# design.net
KiCad netlist of a schematic drawn in EasyEDA
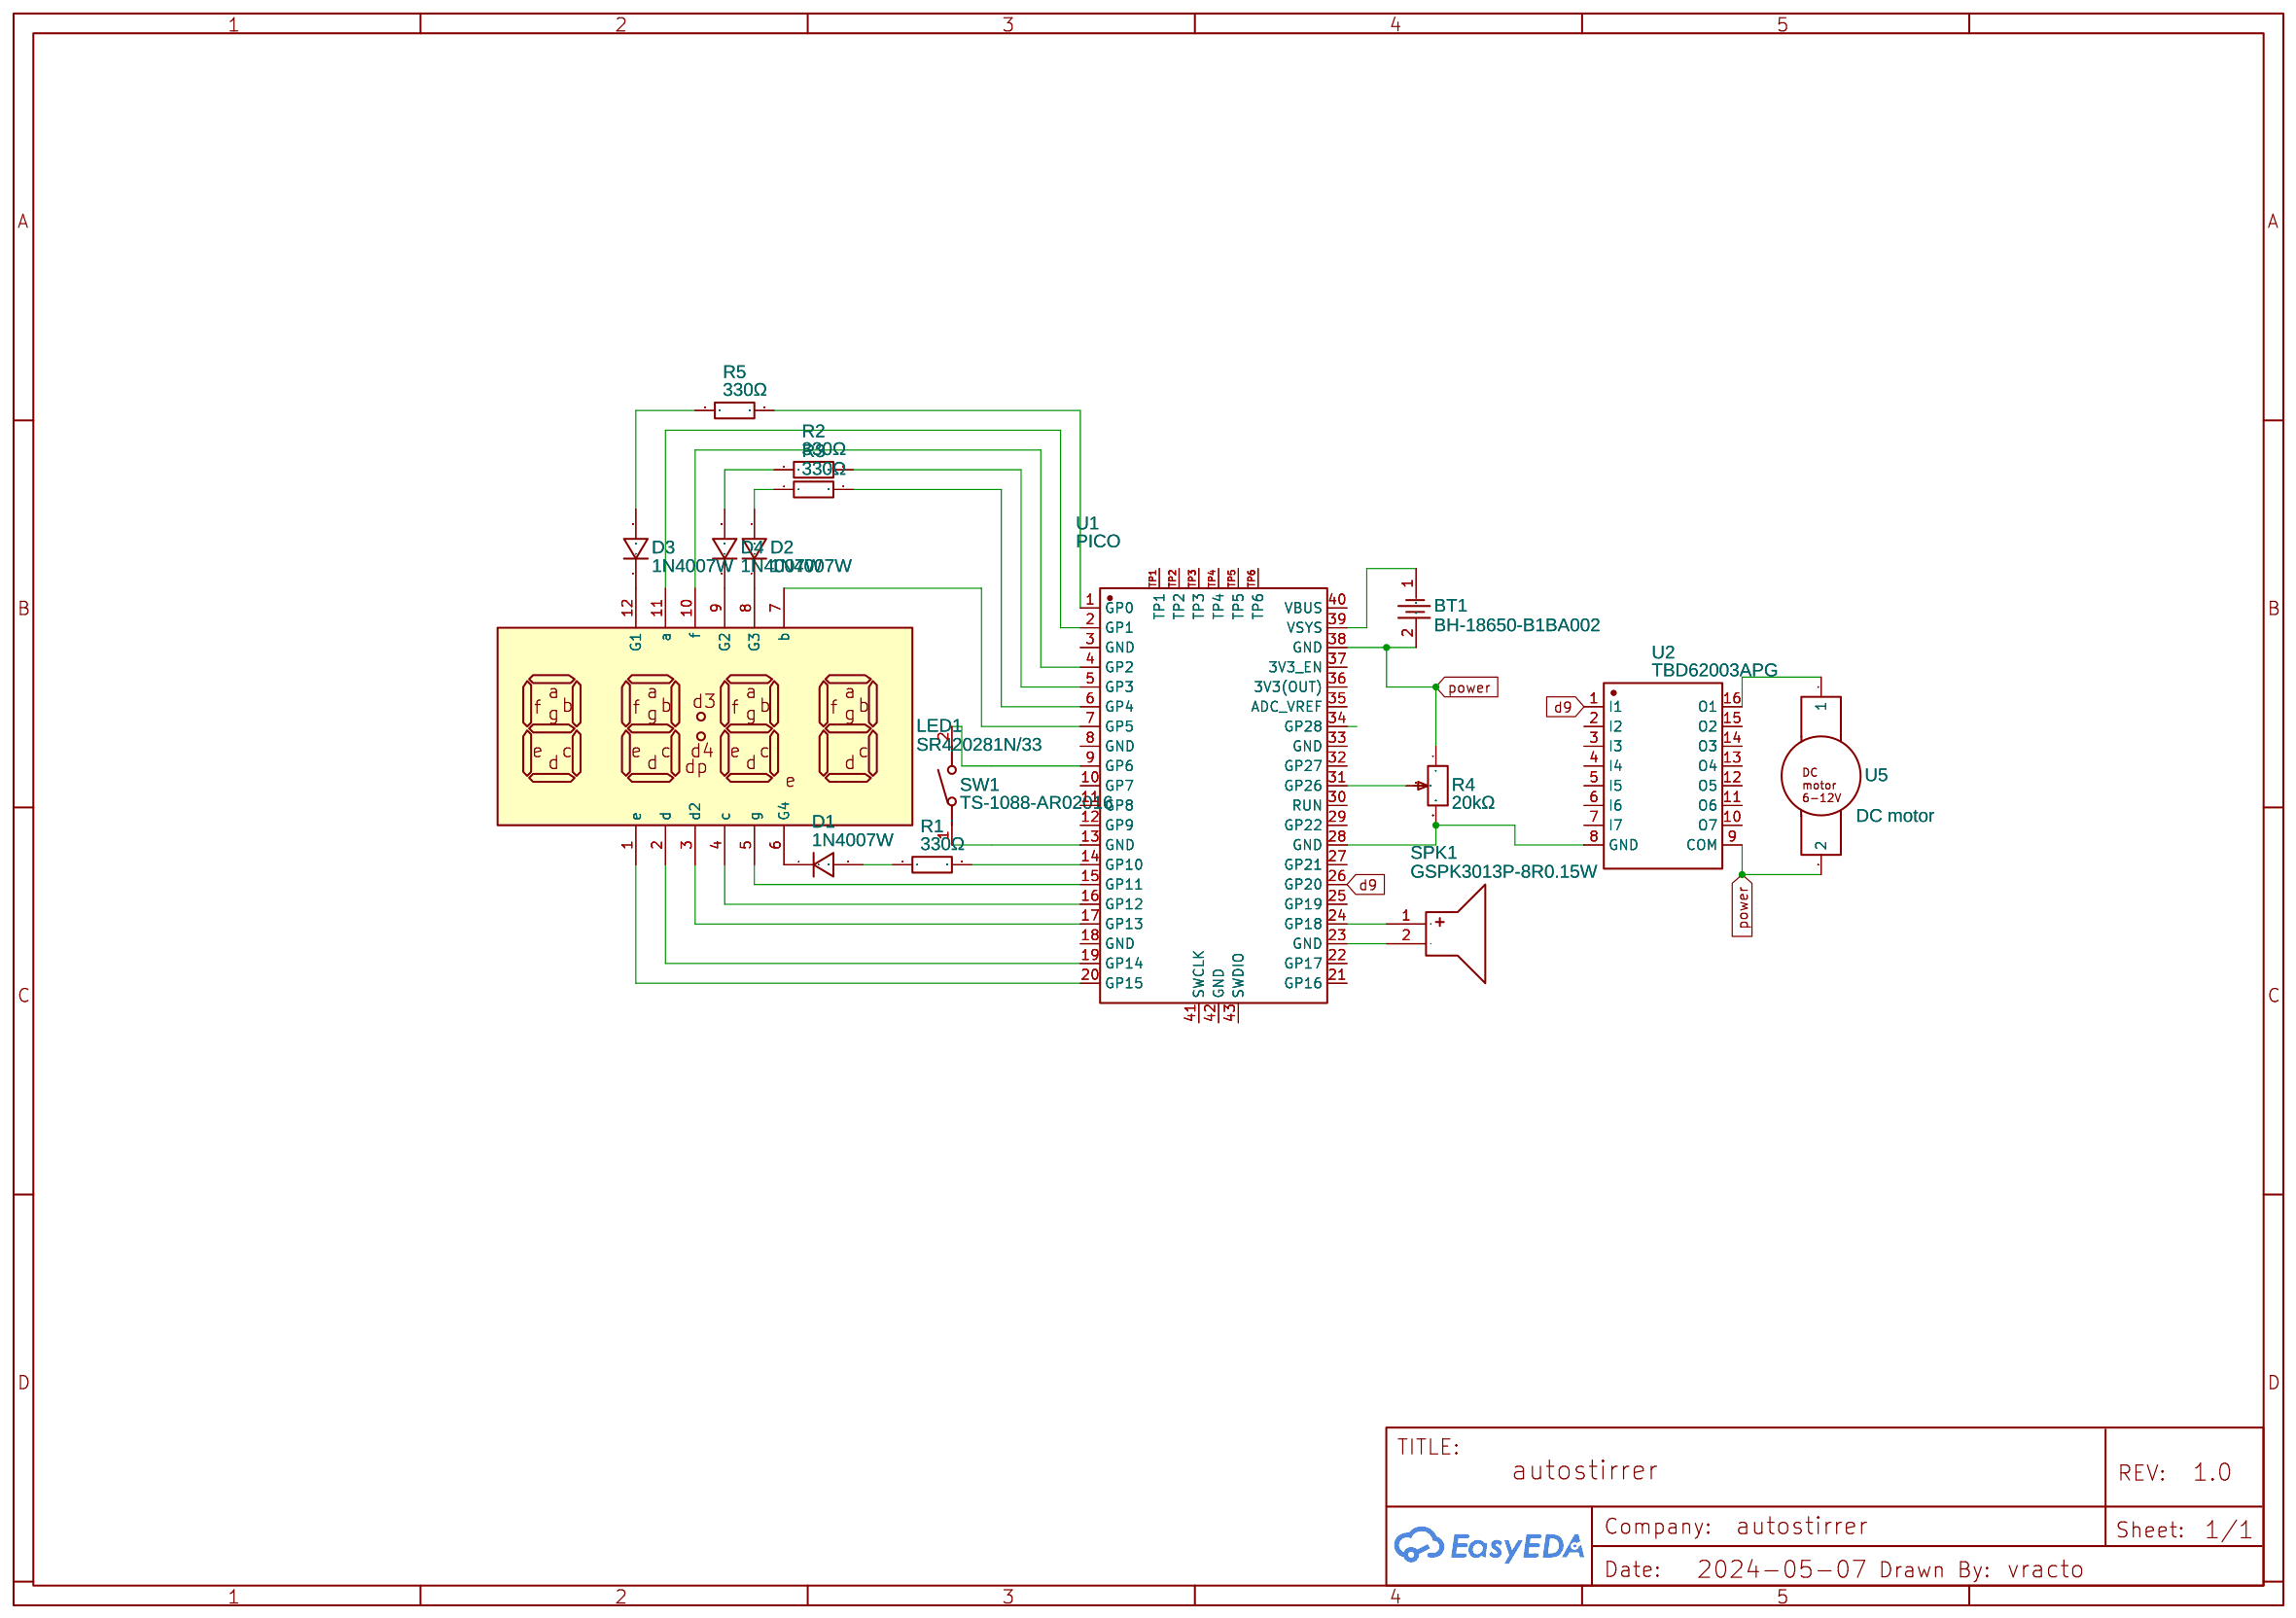
[diagram p0: schematic sheet]

(export (version "E")
  (design (tool "Eeschema 10.0.6"))
  (components
    (comp (ref "BT1")
      (value "BH-18650-B1BA002")
      (fields (field (name "Manufacturer") "MYOUNG(美阳)"))
      (libsource (lib "") (part "BH-18650-B1BA002"))
    )
    (comp (ref "D1")
      (value "1N4007W")
      (fields (field (name "Manufacturer") "BLUE ROCKET"))
      (libsource (lib "") (part "1N4007W_1"))
    )
    (comp (ref "D2")
      (value "1N4007W")
      (fields (field (name "Manufacturer") "BLUE ROCKET"))
      (libsource (lib "") (part "1N4007W"))
    )
    (comp (ref "D3")
      (value "1N4007W")
      (fields (field (name "Manufacturer") "BLUE ROCKET"))
      (libsource (lib "") (part "1N4007W"))
    )
    (comp (ref "D4")
      (value "1N4007W")
      (fields (field (name "Manufacturer") "BLUE ROCKET"))
      (libsource (lib "") (part "1N4007W"))
    )
    (comp (ref "LED1")
      (value "SR420281N/33")
      (fields (field (name "Manufacturer Part") "SR420281N") (field (name "Manufacturer") "ARKLED(方舟)"))
      (libsource (lib "") (part "SR420281N/33"))
    )
    (comp (ref "R1")
      (value "330Ω")
      (fields (field (name "Manufacturer Part") "MFR-25FTE52-330R") (field (name "Manufacturer") "YAGEO(国巨)"))
      (libsource (lib "") (part "MFR-25FTE52-330R"))
    )
    (comp (ref "R2")
      (value "330Ω")
      (fields (field (name "Manufacturer Part") "MFR-25FTE52-330R") (field (name "Manufacturer") "YAGEO(国巨)"))
      (libsource (lib "") (part "MFR-25FTE52-330R"))
    )
    (comp (ref "R3")
      (value "330Ω")
      (fields (field (name "Manufacturer Part") "MFR-25FTE52-330R") (field (name "Manufacturer") "YAGEO(国巨)"))
      (libsource (lib "") (part "MFR-25FTE52-330R"))
    )
    (comp (ref "R4")
      (value "20kΩ")
      (fields (field (name "Manufacturer Part") "3296W-1-203LF") (field (name "Manufacturer") "BOURNS"))
      (libsource (lib "") (part "3296W-1-203LF"))
    )
    (comp (ref "R5")
      (value "330Ω")
      (fields (field (name "Manufacturer Part") "MFR-25FTE52-330R") (field (name "Manufacturer") "YAGEO(国巨)"))
      (libsource (lib "") (part "MFR-25FTE52-330R"))
    )
    (comp (ref "SPK1")
      (value "GSPK3013P-8R0.15W")
      (fields (field (name "Manufacturer") "INGHAi(赢海)"))
      (libsource (lib "") (part "GSPK3013P-8R0.15W"))
    )
    (comp (ref "SW1")
      (value "TS-1088-AR02016")
      (fields (field (name "Manufacturer") "XUNPU(讯普)"))
      (libsource (lib "") (part "TS-1088-AR02016"))
    )
    (comp (ref "U1")
      (value "PICO")
      (fields (field (name "Manufacturer") "Raspberry Pi(树莓派)"))
      (libsource (lib "") (part "PICO"))
    )
    (comp (ref "U2")
      (value "TBD62003APG")
      (fields
        (field (name "Manufacturer Part") "TBD62003APG(Z,HZ)")
        (field (name "Manufacturer") "TOSHIBA(东芝)")
      )
      (libsource (lib "") (part "TBD62003APG"))
    )
    (comp (ref "U5")
      (value "DC motor")
      (fields (field (name "Manufacturer Part") "?"))
      (libsource (lib "") (part "Unknown_915_-420"))
    )
  )
  (nets
    (net (code "1") (name "Net-(D1-Pad2)") (class "Default")
      (node (ref "D1") (pin "2") (pinfunction "2_2") (pintype "unspecified"))
      (node (ref "R1") (pin "1") (pinfunction "1_1") (pintype "input"))
    )
    (net (code "2") (name "Net-(D2-Pad2)") (class "Default")
      (node (ref "D2") (pin "2") (pinfunction "2_2") (pintype "unspecified"))
      (node (ref "R3") (pin "1") (pinfunction "1_1") (pintype "input"))
    )
    (net (code "3") (name "Net-(D3-Pad2)") (class "Default")
      (node (ref "D3") (pin "2") (pinfunction "2_2") (pintype "unspecified"))
      (node (ref "R5") (pin "1") (pinfunction "1_1") (pintype "input"))
    )
    (net (code "4") (name "Net-(D4-Pad2)") (class "Default")
      (node (ref "D4") (pin "2") (pinfunction "2_2") (pintype "unspecified"))
      (node (ref "R2") (pin "1") (pinfunction "1_1") (pintype "input"))
    )
    (net (code "5") (name "Net-(LED1-G1)") (class "Default")
      (node (ref "D3") (pin "1") (pinfunction "1_1") (pintype "unspecified"))
      (node (ref "LED1") (pin "12") (pinfunction "G1_12") (pintype "input"))
    )
    (net (code "6") (name "Net-(LED1-G2)") (class "Default")
      (node (ref "D4") (pin "1") (pinfunction "1_1") (pintype "unspecified"))
      (node (ref "LED1") (pin "9") (pinfunction "G2_9") (pintype "input"))
    )
    (net (code "7") (name "Net-(LED1-G3)") (class "Default")
      (node (ref "D2") (pin "1") (pinfunction "1_1") (pintype "unspecified"))
      (node (ref "LED1") (pin "8") (pinfunction "G3_8") (pintype "input"))
    )
    (net (code "8") (name "Net-(LED1-G4)") (class "Default")
      (node (ref "D1") (pin "1") (pinfunction "1_1") (pintype "unspecified"))
      (node (ref "LED1") (pin "6") (pinfunction "G4_6") (pintype "input"))
    )
    (net (code "9") (name "Net-(LED1-a)") (class "Default")
      (node (ref "LED1") (pin "11") (pinfunction "a_11") (pintype "input"))
      (node (ref "U1") (pin "2") (pinfunction "GP1_2") (pintype "unspecified"))
    )
    (net (code "10") (name "Net-(LED1-b)") (class "Default")
      (node (ref "LED1") (pin "7") (pinfunction "b_7") (pintype "input"))
      (node (ref "U1") (pin "7") (pinfunction "GP5_7") (pintype "unspecified"))
    )
    (net (code "11") (name "Net-(LED1-c)") (class "Default")
      (node (ref "LED1") (pin "4") (pinfunction "c_4") (pintype "input"))
      (node (ref "U1") (pin "16") (pinfunction "GP12_16") (pintype "unspecified"))
    )
    (net (code "12") (name "Net-(LED1-d)") (class "Default")
      (node (ref "LED1") (pin "2") (pinfunction "d_2") (pintype "input"))
      (node (ref "U1") (pin "19") (pinfunction "GP14_19") (pintype "unspecified"))
    )
    (net (code "13") (name "Net-(LED1-d2)") (class "Default")
      (node (ref "LED1") (pin "3") (pinfunction "d2_3") (pintype "input"))
      (node (ref "U1") (pin "17") (pinfunction "GP13_17") (pintype "unspecified"))
    )
    (net (code "14") (name "Net-(LED1-e)") (class "Default")
      (node (ref "LED1") (pin "1") (pinfunction "e_1") (pintype "input"))
      (node (ref "U1") (pin "20") (pinfunction "GP15_20") (pintype "unspecified"))
    )
    (net (code "15") (name "Net-(LED1-f)") (class "Default")
      (node (ref "LED1") (pin "10") (pinfunction "f_10") (pintype "input"))
      (node (ref "U1") (pin "4") (pinfunction "GP2_4") (pintype "unspecified"))
    )
    (net (code "16") (name "Net-(LED1-g)") (class "Default")
      (node (ref "LED1") (pin "5") (pinfunction "g_5") (pintype "input"))
      (node (ref "U1") (pin "15") (pinfunction "GP11_15") (pintype "unspecified"))
    )
    (net (code "17") (name "Net-(SPK1-+)") (class "Default")
      (node (ref "SPK1") (pin "1") (pinfunction "+_1") (pintype "unspecified"))
      (node (ref "U1") (pin "24") (pinfunction "GP18_24") (pintype "unspecified"))
    )
    (net (code "18") (name "Net-(SPK1--)") (class "Default")
      (node (ref "SPK1") (pin "2") (pinfunction "-_2") (pintype "unspecified"))
      (node (ref "U1") (pin "23") (pinfunction "GND_23") (pintype "unspecified"))
    )
    (net (code "19") (name "Net-(SW1-Pad1)") (class "Default")
      (node (ref "SW1") (pin "1") (pinfunction "1_1") (pintype "unspecified"))
      (node (ref "U1") (pin "13") (pinfunction "GND_13") (pintype "unspecified"))
    )
    (net (code "20") (name "Net-(U1-GP0)") (class "Default")
      (node (ref "R5") (pin "2") (pinfunction "2_2") (pintype "input"))
      (node (ref "U1") (pin "1") (pinfunction "GP0_1") (pintype "unspecified"))
    )
    (net (code "21") (name "Net-(U1-GP3)") (class "Default")
      (node (ref "R2") (pin "2") (pinfunction "2_2") (pintype "input"))
      (node (ref "U1") (pin "5") (pinfunction "GP3_5") (pintype "unspecified"))
    )
    (net (code "22") (name "Net-(U1-GP4)") (class "Default")
      (node (ref "R3") (pin "2") (pinfunction "2_2") (pintype "input"))
      (node (ref "U1") (pin "6") (pinfunction "GP4_6") (pintype "unspecified"))
    )
    (net (code "23") (name "Net-(U1-GP6)") (class "Default")
      (node (ref "SW1") (pin "2") (pinfunction "2_2") (pintype "unspecified"))
      (node (ref "U1") (pin "9") (pinfunction "GP6_9") (pintype "unspecified"))
    )
    (net (code "24") (name "Net-(U1-GP10)") (class "Default")
      (node (ref "R1") (pin "2") (pinfunction "2_2") (pintype "input"))
      (node (ref "U1") (pin "14") (pinfunction "GP10_14") (pintype "unspecified"))
    )
    (net (code "25") (name "Net-(U1-GP26)") (class "Default")
      (node (ref "R4") (pin "2") (pinfunction "2_2") (pintype "input"))
      (node (ref "U1") (pin "31") (pinfunction "GP26_31") (pintype "unspecified"))
    )
    (net (code "26") (name "Net-(U1-VSYS)") (class "Default")
      (node (ref "BT1") (pin "1") (pinfunction "1_1") (pintype "input"))
      (node (ref "U1") (pin "39") (pinfunction "VSYS_39") (pintype "unspecified"))
    )
    (net (code "27") (name "Net-(U2-GND)") (class "Default")
      (node (ref "R4") (pin "3") (pinfunction "3_3") (pintype "input"))
      (node (ref "U1") (pin "28") (pinfunction "GND_28") (pintype "unspecified"))
      (node (ref "U2") (pin "8") (pinfunction "GND_8") (pintype "unspecified"))
    )
    (net (code "28") (name "Net-(U2-O1)") (class "Default")
      (node (ref "U2") (pin "16") (pinfunction "O1_16") (pintype "unspecified"))
      (node (ref "U5") (pin "1") (pinfunction "1_1") (pintype "unspecified"))
    )
    (net (code "29") (name "d9") (class "Default")
      (node (ref "U1") (pin "26") (pinfunction "GP20_26") (pintype "unspecified"))
      (node (ref "U2") (pin "1") (pinfunction "I1_1") (pintype "unspecified"))
    )
    (net (code "30") (name "power") (class "Default")
      (node (ref "BT1") (pin "2") (pinfunction "2_2") (pintype "input"))
      (node (ref "R4") (pin "1") (pinfunction "1_1") (pintype "input"))
      (node (ref "U1") (pin "38") (pinfunction "GND_38") (pintype "unspecified"))
      (node (ref "U2") (pin "9") (pinfunction "COM_9") (pintype "unspecified"))
      (node (ref "U5") (pin "2") (pinfunction "2_2") (pintype "unspecified"))
    )
    (net (code "31") (name "unconnected-(U1-3V3(OUT)-Pad36)") (class "Default")
      (node (ref "U1") (pin "36") (pinfunction "3V3(OUT)_36") (pintype "unspecified"))
    )
    (net (code "32") (name "unconnected-(U1-3V3_EN-Pad37)") (class "Default")
      (node (ref "U1") (pin "37") (pinfunction "3V3_EN_37") (pintype "unspecified"))
    )
    (net (code "33") (name "unconnected-(U1-ADC_VREF-Pad35)") (class "Default")
      (node (ref "U1") (pin "35") (pinfunction "ADC_VREF_35") (pintype "unspecified"))
    )
    (net (code "34") (name "unconnected-(U1-GND-Pad3)") (class "Default")
      (node (ref "U1") (pin "3") (pinfunction "GND_3") (pintype "unspecified"))
    )
    (net (code "35") (name "unconnected-(U1-GND-Pad8)") (class "Default")
      (node (ref "U1") (pin "8") (pinfunction "GND_8") (pintype "unspecified"))
    )
    (net (code "36") (name "unconnected-(U1-GND-Pad18)") (class "Default")
      (node (ref "U1") (pin "18") (pinfunction "GND_18") (pintype "unspecified"))
    )
    (net (code "37") (name "unconnected-(U1-GND-Pad33)") (class "Default")
      (node (ref "U1") (pin "33") (pinfunction "GND_33") (pintype "unspecified"))
    )
    (net (code "38") (name "unconnected-(U1-GND-Pad42)") (class "Default")
      (node (ref "U1") (pin "42") (pinfunction "GND_42") (pintype "unspecified"))
    )
    (net (code "39") (name "unconnected-(U1-GP7-Pad10)") (class "Default")
      (node (ref "U1") (pin "10") (pinfunction "GP7_10") (pintype "unspecified"))
    )
    (net (code "40") (name "unconnected-(U1-GP8-Pad11)") (class "Default")
      (node (ref "U1") (pin "11") (pinfunction "GP8_11") (pintype "unspecified"))
    )
    (net (code "41") (name "unconnected-(U1-GP9-Pad12)") (class "Default")
      (node (ref "U1") (pin "12") (pinfunction "GP9_12") (pintype "unspecified"))
    )
    (net (code "42") (name "unconnected-(U1-GP16-Pad21)") (class "Default")
      (node (ref "U1") (pin "21") (pinfunction "GP16_21") (pintype "unspecified"))
    )
    (net (code "43") (name "unconnected-(U1-GP17-Pad22)") (class "Default")
      (node (ref "U1") (pin "22") (pinfunction "GP17_22") (pintype "unspecified"))
    )
    (net (code "44") (name "unconnected-(U1-GP19-Pad25)") (class "Default")
      (node (ref "U1") (pin "25") (pinfunction "GP19_25") (pintype "unspecified"))
    )
    (net (code "45") (name "unconnected-(U1-GP21-Pad27)") (class "Default")
      (node (ref "U1") (pin "27") (pinfunction "GP21_27") (pintype "unspecified"))
    )
    (net (code "46") (name "unconnected-(U1-GP22-Pad29)") (class "Default")
      (node (ref "U1") (pin "29") (pinfunction "GP22_29") (pintype "unspecified"))
    )
    (net (code "47") (name "unconnected-(U1-GP27-Pad32)") (class "Default")
      (node (ref "U1") (pin "32") (pinfunction "GP27_32") (pintype "unspecified"))
    )
    (net (code "48") (name "unconnected-(U1-GP28-Pad34)") (class "Default")
      (node (ref "U1") (pin "34") (pinfunction "GP28_34") (pintype "unspecified"))
    )
    (net (code "49") (name "unconnected-(U1-PadTP1)") (class "Default")
      (node (ref "U1") (pin "TP1") (pinfunction "TP1_TP1") (pintype "unspecified"))
    )
    (net (code "50") (name "unconnected-(U1-PadTP2)") (class "Default")
      (node (ref "U1") (pin "TP2") (pinfunction "TP2_TP2") (pintype "unspecified"))
    )
    (net (code "51") (name "unconnected-(U1-PadTP3)") (class "Default")
      (node (ref "U1") (pin "TP3") (pinfunction "TP3_TP3") (pintype "unspecified"))
    )
    (net (code "52") (name "unconnected-(U1-PadTP4)") (class "Default")
      (node (ref "U1") (pin "TP4") (pinfunction "TP4_TP4") (pintype "unspecified"))
    )
    (net (code "53") (name "unconnected-(U1-PadTP5)") (class "Default")
      (node (ref "U1") (pin "TP5") (pinfunction "TP5_TP5") (pintype "unspecified"))
    )
    (net (code "54") (name "unconnected-(U1-PadTP6)") (class "Default")
      (node (ref "U1") (pin "TP6") (pinfunction "TP6_TP6") (pintype "unspecified"))
    )
    (net (code "55") (name "unconnected-(U1-RUN-Pad30)") (class "Default")
      (node (ref "U1") (pin "30") (pinfunction "RUN_30") (pintype "unspecified"))
    )
    (net (code "56") (name "unconnected-(U1-SWCLK-Pad41)") (class "Default")
      (node (ref "U1") (pin "41") (pinfunction "SWCLK_41") (pintype "unspecified"))
    )
    (net (code "57") (name "unconnected-(U1-SWDIO-Pad43)") (class "Default")
      (node (ref "U1") (pin "43") (pinfunction "SWDIO_43") (pintype "unspecified"))
    )
    (net (code "58") (name "unconnected-(U1-VBUS-Pad40)") (class "Default")
      (node (ref "U1") (pin "40") (pinfunction "VBUS_40") (pintype "unspecified"))
    )
    (net (code "59") (name "unconnected-(U2-I2-Pad2)") (class "Default")
      (node (ref "U2") (pin "2") (pinfunction "I2_2") (pintype "unspecified"))
    )
    (net (code "60") (name "unconnected-(U2-I3-Pad3)") (class "Default")
      (node (ref "U2") (pin "3") (pinfunction "I3_3") (pintype "unspecified"))
    )
    (net (code "61") (name "unconnected-(U2-I4-Pad4)") (class "Default")
      (node (ref "U2") (pin "4") (pinfunction "I4_4") (pintype "unspecified"))
    )
    (net (code "62") (name "unconnected-(U2-I5-Pad5)") (class "Default")
      (node (ref "U2") (pin "5") (pinfunction "I5_5") (pintype "unspecified"))
    )
    (net (code "63") (name "unconnected-(U2-I6-Pad6)") (class "Default")
      (node (ref "U2") (pin "6") (pinfunction "I6_6") (pintype "unspecified"))
    )
    (net (code "64") (name "unconnected-(U2-I7-Pad7)") (class "Default")
      (node (ref "U2") (pin "7") (pinfunction "I7_7") (pintype "unspecified"))
    )
    (net (code "65") (name "unconnected-(U2-O2-Pad15)") (class "Default")
      (node (ref "U2") (pin "15") (pinfunction "O2_15") (pintype "unspecified"))
    )
    (net (code "66") (name "unconnected-(U2-O3-Pad14)") (class "Default")
      (node (ref "U2") (pin "14") (pinfunction "O3_14") (pintype "unspecified"))
    )
    (net (code "67") (name "unconnected-(U2-O4-Pad13)") (class "Default")
      (node (ref "U2") (pin "13") (pinfunction "O4_13") (pintype "unspecified"))
    )
    (net (code "68") (name "unconnected-(U2-O5-Pad12)") (class "Default")
      (node (ref "U2") (pin "12") (pinfunction "O5_12") (pintype "unspecified"))
    )
    (net (code "69") (name "unconnected-(U2-O6-Pad11)") (class "Default")
      (node (ref "U2") (pin "11") (pinfunction "O6_11") (pintype "unspecified"))
    )
    (net (code "70") (name "unconnected-(U2-O7-Pad10)") (class "Default")
      (node (ref "U2") (pin "10") (pinfunction "O7_10") (pintype "unspecified"))
    )
  )
)
